# MCU.net
KiCad netlist of a schematic drawn in Altium Designer
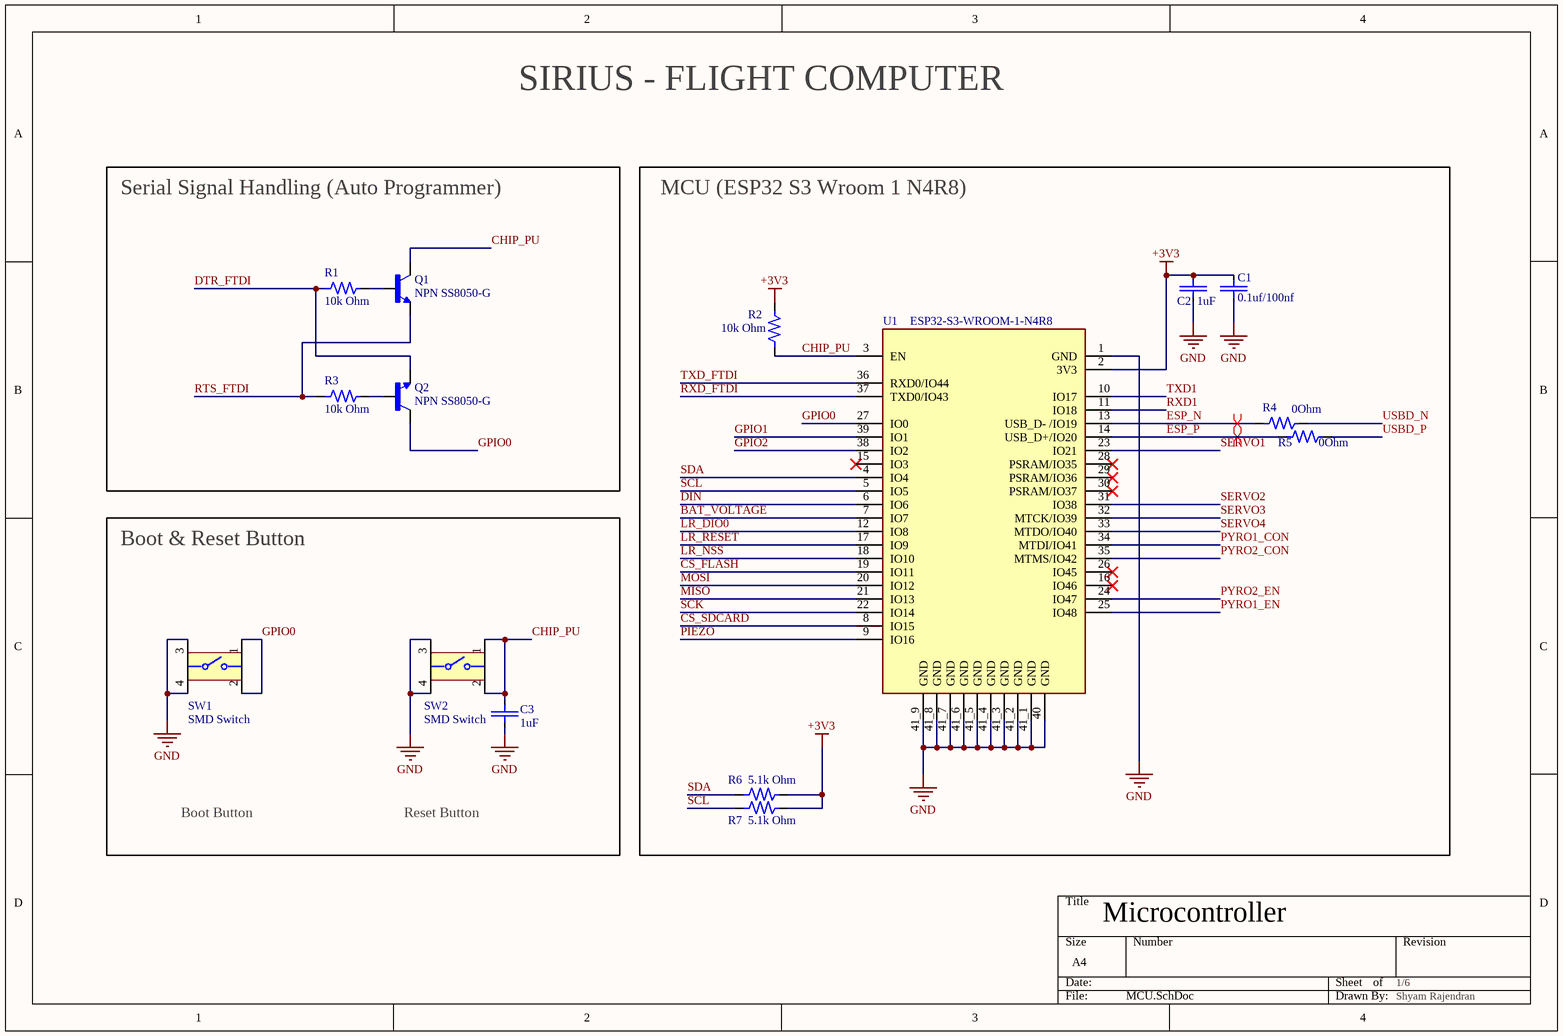
[diagram p0: MCU.SchDoc]

(export (version "E")
  (design (tool "Eeschema 10.0.6"))
  (components
    (comp (ref "C1")
      (value "0.1uf/100nf")
      (footprint "0.1uF Capacitor")
      (description "0.1 uF, Multilayer Ceramic Capacitor, 50 V, ï¿½ 10%, X7R, 0805 [2012 Metric]")
      (fields
        (field (name "MANUFACTURER") "Yageo")
        (field (name "MANUFACTURER PART NUMBER") "CC0805KRX7R9BB104")
      )
      (libsource (lib "Sirius") (part "CC0805KRX7R9BB104"))
    )
    (comp (ref "C2")
      (value "1uF")
      (footprint "10uf Capacitor")
      (fields
        (field (name "MANUFACTURER") "Yageo")
        (field (name "MANUFACTURER PART NUMBER") "CC0805KKX7R6BB105")
      )
      (libsource (lib "Sirius") (part "CC0805KKX7R6BB105"))
    )
    (comp (ref "C3")
      (value "1uF")
      (footprint "10uf Capacitor")
      (fields
        (field (name "MANUFACTURER") "Yageo")
        (field (name "MANUFACTURER PART NUMBER") "CC0805KKX7R6BB105")
      )
      (libsource (lib "Sirius") (part "CC0805KKX7R6BB105"))
    )
    (comp (ref "Q1")
      (value "NPN SS8050-G")
      (footprint "Transistor_SS8050-G")
      (description "Trans Gp Bjt NPN 25V 1.5A 300MW 3-PIN SOT-23 T/r")
      (fields (field (name "MANUFACTURER") "Comchip") (field (name "MANUFACTURER PART NUMBER") "SS8050-G"))
      (libsource (lib "") (part "SS8050-G_1"))
    )
    (comp (ref "Q2")
      (value "NPN SS8050-G")
      (footprint "Transistor_SS8050-G")
      (description "Trans Gp Bjt NPN 25V 1.5A 300MW 3-PIN SOT-23 T/r")
      (fields (field (name "MANUFACTURER") "Comchip") (field (name "MANUFACTURER PART NUMBER") "SS8050-G"))
      (libsource (lib "Sirius") (part "SS8050-G"))
    )
    (comp (ref "R1")
      (value "10k Ohm")
      (footprint "RESC2013X60X35ML10T20")
      (description "10 kOhm, SMD Chip Resistor, ï¿½ 1%, 125 mW, 0805 [2012 Metric], Thick Film, General Purpose")
      (fields
        (field (name "MANUFACTURER") "Yageo")
        (field (name "MANUFACTURER PART NUMBER") "RC0805FR-0710KL")
      )
      (libsource (lib "Sirius") (part "RC0805FR-0710KL"))
    )
    (comp (ref "R2")
      (value "10k Ohm")
      (footprint "RESC2013X60X35ML10T20")
      (description "10 kOhm, SMD Chip Resistor, ï¿½ 1%, 125 mW, 0805 [2012 Metric], Thick Film, General Purpose")
      (fields
        (field (name "MANUFACTURER") "Yageo")
        (field (name "MANUFACTURER PART NUMBER") "RC0805FR-0710KL")
      )
      (libsource (lib "Sirius") (part "RC0805FR-0710KL"))
    )
    (comp (ref "R3")
      (value "10k Ohm")
      (footprint "RESC2013X60X35ML10T20")
      (description "10 kOhm, SMD Chip Resistor, ï¿½ 1%, 125 mW, 0805 [2012 Metric], Thick Film, General Purpose")
      (fields
        (field (name "MANUFACTURER") "Yageo")
        (field (name "MANUFACTURER PART NUMBER") "RC0805FR-0710KL")
      )
      (libsource (lib "Sirius") (part "RC0805FR-0710KL"))
    )
    (comp (ref "R4")
      (value "0Ohm")
      (footprint "1k 0805 Resistor")
      (description "0 Ohm Resistor, Jumper, 0805 [2012 Metric], Thick Film, 125 mW, Surface Mount")
      (fields
        (field (name "MANUFACTURER") "Vishay")
        (field (name "MANUFACTURER PART NUMBER") "CRCW08050000Z0EA")
      )
      (libsource (lib "Sirius") (part "CRCW08050000Z0EA"))
    )
    (comp (ref "R5")
      (value "0Ohm")
      (footprint "1k 0805 Resistor")
      (description "0 Ohm Resistor, Jumper, 0805 [2012 Metric], Thick Film, 125 mW, Surface Mount")
      (fields
        (field (name "MANUFACTURER") "Vishay")
        (field (name "MANUFACTURER PART NUMBER") "CRCW08050000Z0EA")
      )
      (libsource (lib "Sirius") (part "CRCW08050000Z0EA"))
    )
    (comp (ref "R6")
      (value "5.1k Ohm")
      (footprint "RESC2012X60N")
      (description "5.1k Ohm, 0805, 0.125W, 150V, 1% +/-Tol, 100ppm/Cel, Surface Mount")
      (fields
        (field (name "MANUFACTURER") "Yageo")
        (field (name "MANUFACTURER PART NUMBER") "RC0805FR-075K1L")
      )
      (libsource (lib "Sirius") (part "RC0805FR-075K1L"))
    )
    (comp (ref "R7")
      (value "5.1k Ohm")
      (footprint "RESC2012X60N")
      (description "5.1k Ohm, 0805, 0.125W, 150V, 1% +/-Tol, 100ppm/Cel, Surface Mount")
      (fields
        (field (name "MANUFACTURER") "Yageo")
        (field (name "MANUFACTURER PART NUMBER") "RC0805FR-075K1L")
      )
      (libsource (lib "Sirius") (part "RC0805FR-075K1L"))
    )
    (comp (ref "SW1")
      (value "SMD Switch")
      (footprint "Oval Switch")
      (fields
        (field (name "MANUFACTURER") "ITT C&K")
        (field (name "MANUFACTURER PART NUMBER") "PTS810SJG250SMTRLFS")
      )
      (libsource (lib "Sirius") (part "Oval Switch"))
    )
    (comp (ref "SW2")
      (value "SMD Switch")
      (footprint "Oval Switch")
      (fields
        (field (name "MANUFACTURER") "ITT C&K")
        (field (name "MANUFACTURER PART NUMBER") "PTS810SJG250SMTRLFS")
      )
      (libsource (lib "Sirius") (part "Oval Switch"))
    )
    (comp (ref "U1")
      (value "ESP32-S3-WROOM-1-N4R8")
      (footprint "ESP32-S3-WROOM-1-N4")
      (description "SMD Module, ESP32-S3, 4 mb Spi F")
      (fields
        (field (name "MANUFACTURER") "Espressif Systems")
        (field (name "MANUFACTURER PART NUMBER") "ESP32-S3-WROOM-1-N4")
      )
      (libsource (lib "Sirius") (part "ESP32-S3-WROOM-1-N4R8"))
    )
  )
  (nets
    (net (code "1") (name "+3V3") (class "Default")
      (node (ref "C1") (pin "1") (pinfunction "1_1") (pintype "passive"))
      (node (ref "C2") (pin "2") (pinfunction "2_2") (pintype "passive"))
      (node (ref "R2") (pin "2") (pinfunction "2_2") (pintype "passive"))
      (node (ref "R6") (pin "2") (pinfunction "2_2") (pintype "passive"))
      (node (ref "R7") (pin "2") (pinfunction "2_2") (pintype "passive"))
      (node (ref "U1") (pin "2") (pinfunction "3V3_2") (pintype "passive"))
    )
    (net (code "2") (name "/BAT_VOLTAGE") (class "Default")
      (node (ref "U1") (pin "7") (pinfunction "IO7_7") (pintype "passive"))
    )
    (net (code "3") (name "/CHIP_PU") (class "Default")
      (node (ref "C3") (pin "2") (pinfunction "2_2") (pintype "passive"))
      (node (ref "Q1") (pin "3") (pinfunction "C_3") (pintype "passive"))
      (node (ref "R2") (pin "1") (pinfunction "1_1") (pintype "passive"))
      (node (ref "SW2") (pin "1") (pinfunction "1_1") (pintype "passive"))
      (node (ref "SW2") (pin "2") (pinfunction "2_2") (pintype "passive"))
      (node (ref "U1") (pin "3") (pinfunction "EN_3") (pintype "passive"))
    )
    (net (code "4") (name "/CS_FLASH") (class "Default")
      (node (ref "U1") (pin "19") (pinfunction "IO11_19") (pintype "passive"))
    )
    (net (code "5") (name "/CS_SDCARD") (class "Default")
      (node (ref "U1") (pin "8") (pinfunction "IO15_8") (pintype "passive"))
    )
    (net (code "6") (name "/DIN") (class "Default")
      (node (ref "U1") (pin "6") (pinfunction "IO6_6") (pintype "passive"))
    )
    (net (code "7") (name "/DTR_FTDI") (class "Default")
      (node (ref "Q2") (pin "2") (pinfunction "E_2") (pintype "passive"))
      (node (ref "R1") (pin "1") (pinfunction "1_1") (pintype "passive"))
    )
    (net (code "8") (name "/ESP_N") (class "Default")
      (node (ref "R4") (pin "1") (pinfunction "1_1") (pintype "passive"))
      (node (ref "U1") (pin "13") (pinfunction "USB_D-_/IO19_13") (pintype "passive"))
    )
    (net (code "9") (name "/ESP_P") (class "Default")
      (node (ref "R5") (pin "1") (pinfunction "1_1") (pintype "passive"))
      (node (ref "U1") (pin "14") (pinfunction "USB_D+/IO20_14") (pintype "passive"))
    )
    (net (code "10") (name "/GPIO0") (class "Default")
      (node (ref "Q2") (pin "3") (pinfunction "C_3") (pintype "passive"))
      (node (ref "SW1") (pin "1") (pinfunction "1_1") (pintype "passive"))
      (node (ref "SW1") (pin "2") (pinfunction "2_2") (pintype "passive"))
      (node (ref "U1") (pin "27") (pinfunction "IO0_27") (pintype "passive"))
    )
    (net (code "11") (name "/GPIO1") (class "Default")
      (node (ref "U1") (pin "39") (pinfunction "IO1_39") (pintype "passive"))
    )
    (net (code "12") (name "/GPIO2") (class "Default")
      (node (ref "U1") (pin "38") (pinfunction "IO2_38") (pintype "passive"))
    )
    (net (code "13") (name "/LR_DIO0") (class "Default")
      (node (ref "U1") (pin "12") (pinfunction "IO8_12") (pintype "passive"))
    )
    (net (code "14") (name "/LR_NSS") (class "Default")
      (node (ref "U1") (pin "18") (pinfunction "IO10_18") (pintype "passive"))
    )
    (net (code "15") (name "/LR_RESET") (class "Default")
      (node (ref "U1") (pin "17") (pinfunction "IO9_17") (pintype "passive"))
    )
    (net (code "16") (name "/MISO") (class "Default")
      (node (ref "U1") (pin "21") (pinfunction "IO13_21") (pintype "passive"))
    )
    (net (code "17") (name "/MOSI") (class "Default")
      (node (ref "U1") (pin "20") (pinfunction "IO12_20") (pintype "passive"))
    )
    (net (code "18") (name "/PIEZO") (class "Default")
      (node (ref "U1") (pin "9") (pinfunction "IO16_9") (pintype "passive"))
    )
    (net (code "19") (name "/PYRO1_CON") (class "Default")
      (node (ref "U1") (pin "34") (pinfunction "MTDI/IO41_34") (pintype "passive"))
    )
    (net (code "20") (name "/PYRO1_EN") (class "Default")
      (node (ref "U1") (pin "25") (pinfunction "IO48_25") (pintype "passive"))
    )
    (net (code "21") (name "/PYRO2_CON") (class "Default")
      (node (ref "U1") (pin "35") (pinfunction "MTMS/IO42_35") (pintype "passive"))
    )
    (net (code "22") (name "/PYRO2_EN") (class "Default")
      (node (ref "U1") (pin "24") (pinfunction "IO47_24") (pintype "passive"))
    )
    (net (code "23") (name "/RTS_FTDI") (class "Default")
      (node (ref "Q1") (pin "2") (pinfunction "E_2") (pintype "passive"))
      (node (ref "R3") (pin "1") (pinfunction "1_1") (pintype "passive"))
    )
    (net (code "24") (name "/RXD1") (class "Default")
      (node (ref "U1") (pin "11") (pinfunction "IO18_11") (pintype "passive"))
    )
    (net (code "25") (name "/RXD_FTDI") (class "Default")
      (node (ref "U1") (pin "37") (pinfunction "TXD0/IO43_37") (pintype "passive"))
    )
    (net (code "26") (name "/SCK") (class "Default")
      (node (ref "U1") (pin "22") (pinfunction "IO14_22") (pintype "passive"))
    )
    (net (code "27") (name "/SCL") (class "Default")
      (node (ref "R7") (pin "1") (pinfunction "1_1") (pintype "passive"))
      (node (ref "U1") (pin "5") (pinfunction "IO5_5") (pintype "passive"))
    )
    (net (code "28") (name "/SDA") (class "Default")
      (node (ref "R6") (pin "1") (pinfunction "1_1") (pintype "passive"))
      (node (ref "U1") (pin "4") (pinfunction "IO4_4") (pintype "passive"))
    )
    (net (code "29") (name "/SERVO1") (class "Default")
      (node (ref "U1") (pin "23") (pinfunction "IO21_23") (pintype "passive"))
    )
    (net (code "30") (name "/SERVO2") (class "Default")
      (node (ref "U1") (pin "31") (pinfunction "IO38_31") (pintype "passive"))
    )
    (net (code "31") (name "/SERVO3") (class "Default")
      (node (ref "U1") (pin "32") (pinfunction "MTCK/IO39_32") (pintype "passive"))
    )
    (net (code "32") (name "/SERVO4") (class "Default")
      (node (ref "U1") (pin "33") (pinfunction "MTDO/IO40_33") (pintype "passive"))
    )
    (net (code "33") (name "/TXD1") (class "Default")
      (node (ref "U1") (pin "10") (pinfunction "IO17_10") (pintype "passive"))
    )
    (net (code "34") (name "/TXD_FTDI") (class "Default")
      (node (ref "U1") (pin "36") (pinfunction "RXD0/IO44_36") (pintype "passive"))
    )
    (net (code "35") (name "/USBD_N") (class "Default")
      (node (ref "R4") (pin "2") (pinfunction "2_2") (pintype "passive"))
    )
    (net (code "36") (name "/USBD_P") (class "Default")
      (node (ref "R5") (pin "2") (pinfunction "2_2") (pintype "passive"))
    )
    (net (code "37") (name "GND") (class "Default")
      (node (ref "C1") (pin "2") (pinfunction "2_2") (pintype "passive"))
      (node (ref "C2") (pin "1") (pinfunction "1_1") (pintype "passive"))
      (node (ref "C3") (pin "1") (pinfunction "1_1") (pintype "passive"))
      (node (ref "SW1") (pin "3") (pinfunction "3_3") (pintype "passive"))
      (node (ref "SW1") (pin "4") (pinfunction "4_4") (pintype "passive"))
      (node (ref "SW2") (pin "3") (pinfunction "3_3") (pintype "passive"))
      (node (ref "SW2") (pin "4") (pinfunction "4_4") (pintype "passive"))
      (node (ref "U1") (pin "1") (pinfunction "GND_1") (pintype "passive"))
      (node (ref "U1") (pin "40") (pinfunction "GND_40") (pintype "passive"))
      (node (ref "U1") (pin "41_1") (pinfunction "GND_41_1") (pintype "passive"))
      (node (ref "U1") (pin "41_2") (pinfunction "GND_41_2") (pintype "passive"))
      (node (ref "U1") (pin "41_3") (pinfunction "GND_41_3") (pintype "passive"))
      (node (ref "U1") (pin "41_4") (pinfunction "GND_41_4") (pintype "passive"))
      (node (ref "U1") (pin "41_5") (pinfunction "GND_41_5") (pintype "passive"))
      (node (ref "U1") (pin "41_6") (pinfunction "GND_41_6") (pintype "passive"))
      (node (ref "U1") (pin "41_7") (pinfunction "GND_41_7") (pintype "passive"))
      (node (ref "U1") (pin "41_8") (pinfunction "GND_41_8") (pintype "passive"))
      (node (ref "U1") (pin "41_9") (pinfunction "GND_41_9") (pintype "passive"))
    )
    (net (code "38") (name "Net-(Q1-B)") (class "Default")
      (node (ref "Q1") (pin "1") (pinfunction "B_1") (pintype "passive"))
      (node (ref "R1") (pin "2") (pinfunction "2_2") (pintype "passive"))
    )
    (net (code "39") (name "Net-(Q2-B)") (class "Default")
      (node (ref "Q2") (pin "1") (pinfunction "B_1") (pintype "passive"))
      (node (ref "R3") (pin "2") (pinfunction "2_2") (pintype "passive"))
    )
    (net (code "40") (name "unconnected-(U1-IO3-Pad15)") (class "Default")
      (node (ref "U1") (pin "15") (pinfunction "IO3_15") (pintype "passive+no_connect"))
    )
    (net (code "41") (name "unconnected-(U1-IO45-Pad26)") (class "Default")
      (node (ref "U1") (pin "26") (pinfunction "IO45_26") (pintype "passive+no_connect"))
    )
    (net (code "42") (name "unconnected-(U1-IO46-Pad16)") (class "Default")
      (node (ref "U1") (pin "16") (pinfunction "IO46_16") (pintype "passive+no_connect"))
    )
    (net (code "43") (name "unconnected-(U1-PSRAM{slash}IO35-Pad28)") (class "Default")
      (node (ref "U1") (pin "28") (pinfunction "PSRAM/IO35_28") (pintype "passive+no_connect"))
    )
    (net (code "44") (name "unconnected-(U1-PSRAM{slash}IO36-Pad29)") (class "Default")
      (node (ref "U1") (pin "29") (pinfunction "PSRAM/IO36_29") (pintype "passive+no_connect"))
    )
    (net (code "45") (name "unconnected-(U1-PSRAM{slash}IO37-Pad30)") (class "Default")
      (node (ref "U1") (pin "30") (pinfunction "PSRAM/IO37_30") (pintype "passive+no_connect"))
    )
  )
)
